# USB3.net
KiCad netlist of a schematic drawn in Altium Designer
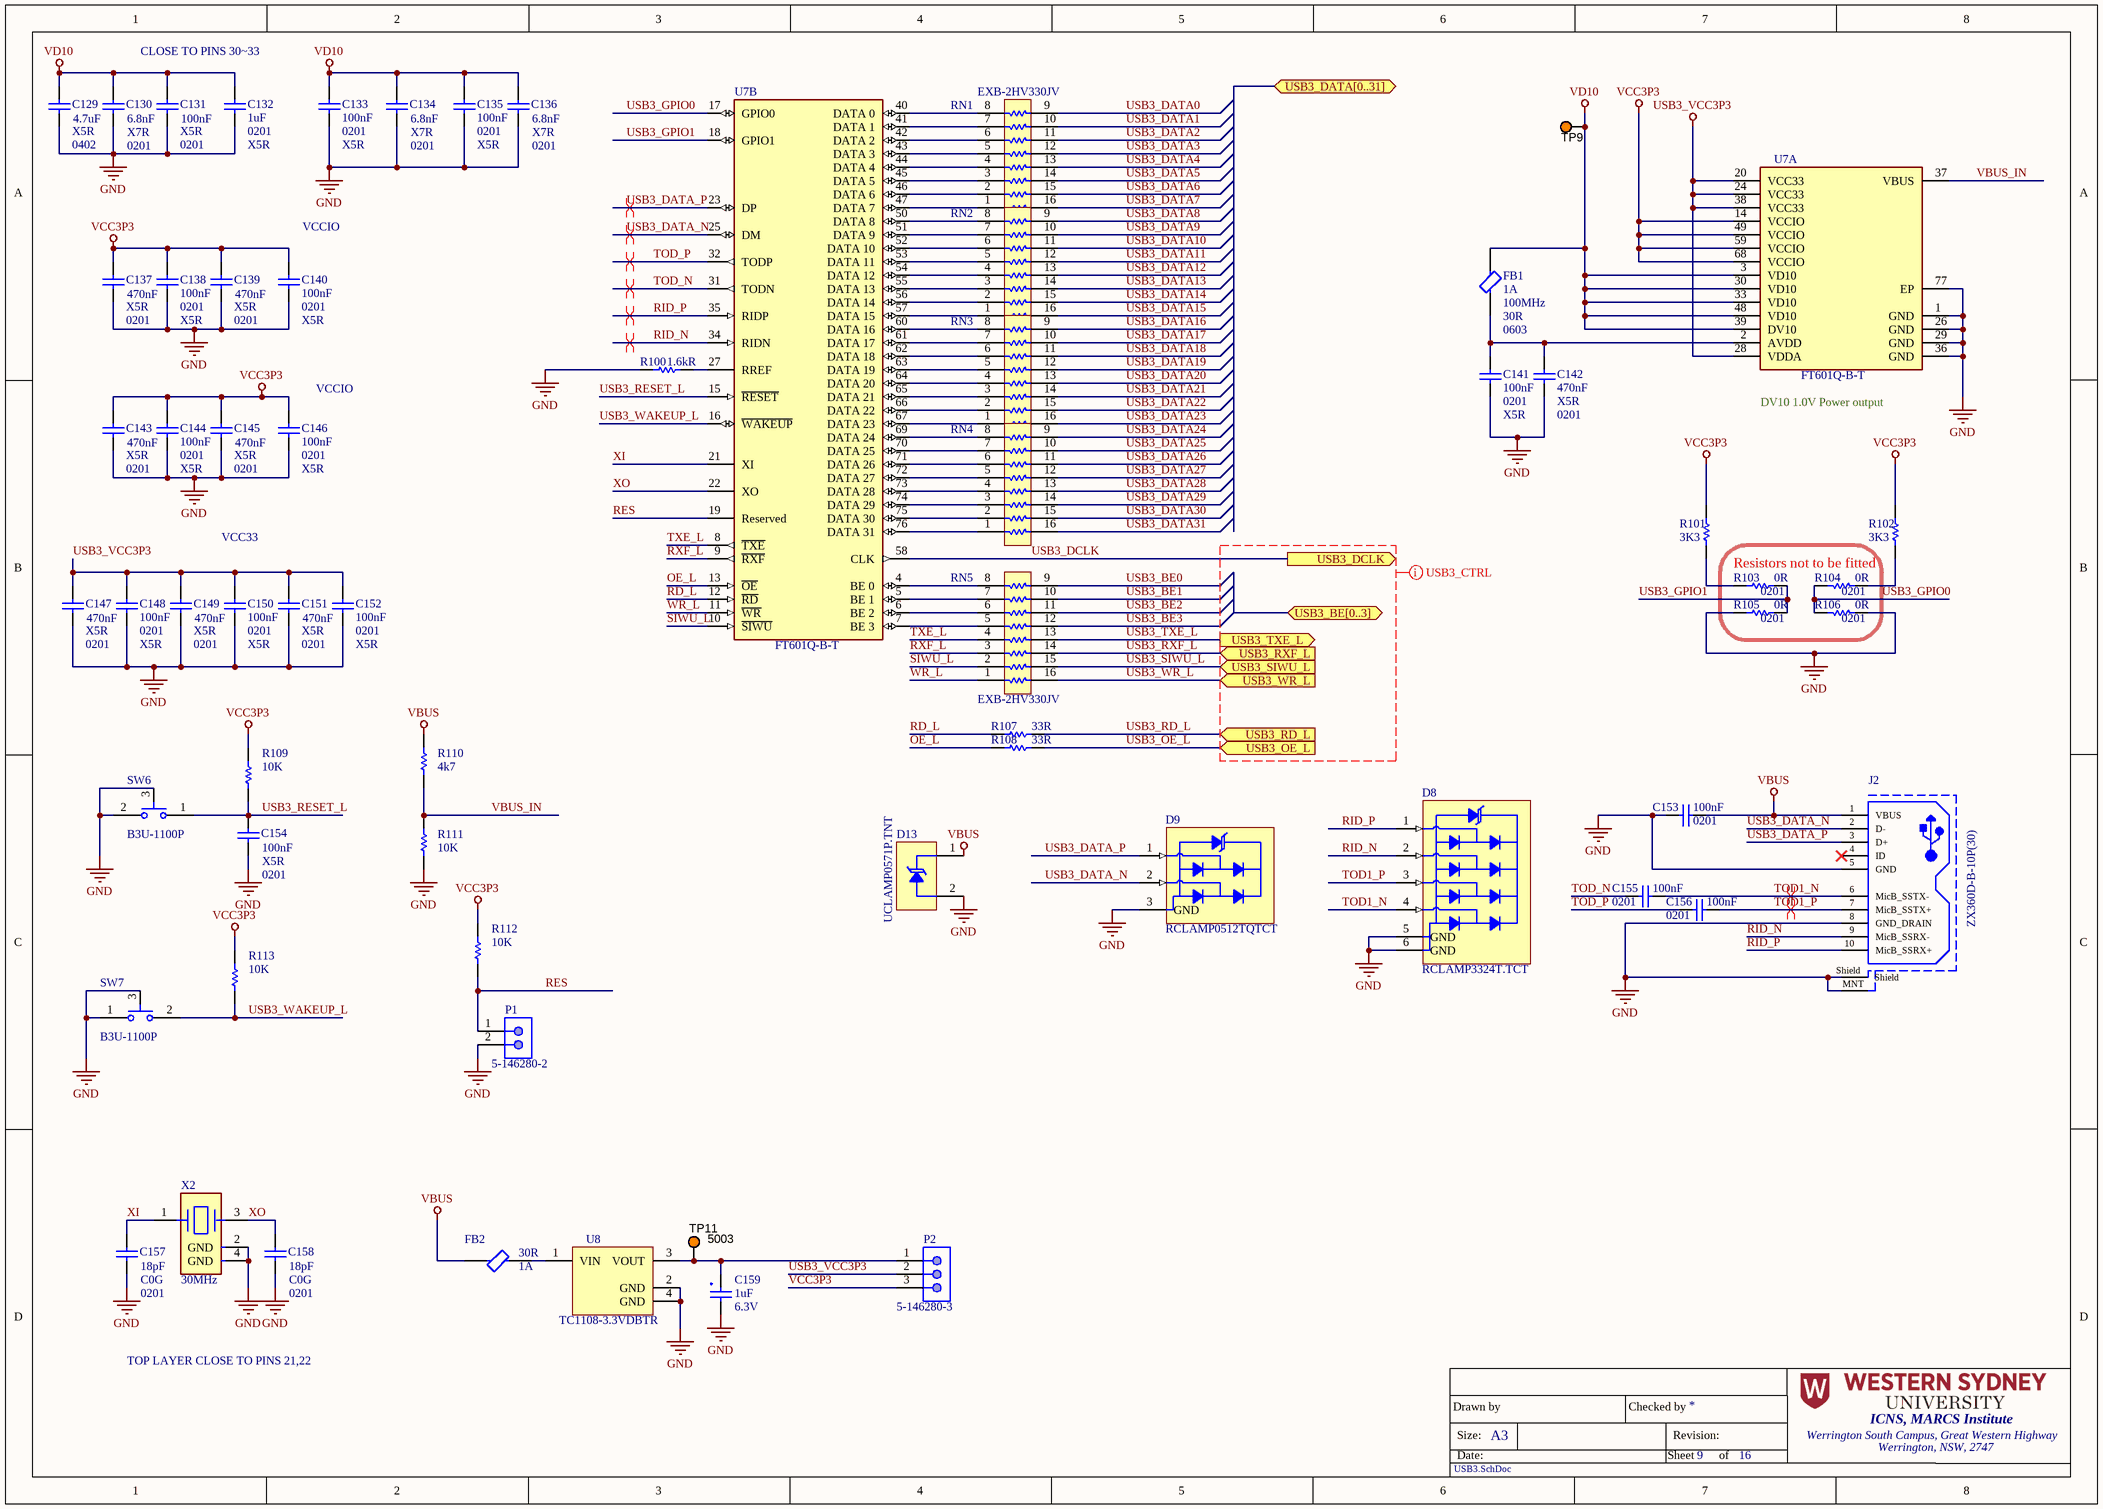
[diagram p0: USB3.SchDoc]

(export (version "E")
  (design (tool "Eeschema 10.0.6"))
  (components
    (comp (ref "C129")
      (value "C1005X5R1A475K050BC")
      (footprint "CAP 0402 (1005)")
      (description "Cap Multilayer Ceramic 4.7uF 10 V X5R ±10 % SMT 0402  C Series")
      (fields
        (field (name "TOLERANCE") "10%")
        (field (name "MANUFACTURER") "TDK")
        (field (name "CAPACITANCE") "4.7uF")
        (field (name "DIELECTRIC") "X5R")
        (field (name "CASE CODE (IMPERIAL)") "0402")
        (field (name "SOURCE") "ICNS_PropheseeLib.SchLib")
      )
      (libsource (lib "") (part "Symbol_2"))
    )
    (comp (ref "C130")
      (value "GRM033R71A682KA01D")
      (footprint "CAP 0201 (0603)")
      (description "Cap Multilayer Ceramic 6.8nF 10V X7R SMT 0201 ±10% Tolerance")
      (fields
        (field (name "TOLERANCE") "10%")
        (field (name "DIELECTRIC") "X7R")
        (field (name "CAPACITANCE") "6.8nF")
        (field (name "CASE CODE (IMPERIAL)") "0201")
        (field (name "MANUFACTURER") "Murata")
        (field (name "SOURCE") "ICNS_PropheseeLib.SchLib")
      )
      (libsource (lib "") (part "Symbol_1"))
    )
    (comp (ref "C131")
      (value "CL03A104KP3NNNC")
      (footprint "CAP 0201 (0603)")
      (description "Cap Ceramic 0.1uF 10V X5R 10% Pad SMD 0201 85C T/R")
      (fields
        (field (name "TOLERANCE") "10%")
        (field (name "MANUFACTURER") "Samsung")
        (field (name "CAPACITANCE") "100nF")
        (field (name "DIELECTRIC") "X5R")
        (field (name "CASE CODE (IMPERIAL)") "0201")
        (field (name "SOURCE") "ICNS_PropheseeLib.SchLib")
      )
      (libsource (lib "Western Sydney University - ICNS") (part "CL03A104KP3NNNC"))
    )
    (comp (ref "C132")
      (value "CL03A105KP3NSNC")
      (footprint "CAP 0201 (0603)")
      (description "Cap Ceramic 1uF 10V X5R 10% Pad SMD 0201 85C T/R")
      (fields
        (field (name "TOLERANCE") "10%")
        (field (name "MANUFACTURER") "Samsung")
        (field (name "CAPACITANCE") "1uF")
        (field (name "CASE CODE (IMPERIAL)") "0201")
        (field (name "DIELECTRIC") "X5R")
        (field (name "SOURCE") "ICNS_PropheseeLib.SchLib")
      )
      (libsource (lib "") (part "Symbol_2"))
    )
    (comp (ref "C133")
      (value "CL03A104KP3NNNC")
      (footprint "CAP 0201 (0603)")
      (description "Cap Ceramic 0.1uF 10V X5R 10% Pad SMD 0201 85C T/R")
      (fields
        (field (name "TOLERANCE") "10%")
        (field (name "MANUFACTURER") "Samsung")
        (field (name "CAPACITANCE") "100nF")
        (field (name "CASE CODE (IMPERIAL)") "0201")
        (field (name "DIELECTRIC") "X5R")
        (field (name "SOURCE") "ICNS_PropheseeLib.SchLib")
      )
      (libsource (lib "Western Sydney University - ICNS") (part "CL03A104KP3NNNC"))
    )
    (comp (ref "C134")
      (value "GRM033R71A682KA01D")
      (footprint "CAP 0201 (0603)")
      (description "Cap Multilayer Ceramic 6.8nF 10V X7R SMT 0201 ±10% Tolerance")
      (fields
        (field (name "TOLERANCE") "10%")
        (field (name "DIELECTRIC") "X7R")
        (field (name "CAPACITANCE") "6.8nF")
        (field (name "CASE CODE (IMPERIAL)") "0201")
        (field (name "MANUFACTURER") "Murata")
        (field (name "SOURCE") "ICNS_PropheseeLib.SchLib")
      )
      (libsource (lib "") (part "Symbol_1"))
    )
    (comp (ref "C135")
      (value "CL03A104KP3NNNC")
      (footprint "CAP 0201 (0603)")
      (description "Cap Ceramic 0.1uF 10V X5R 10% Pad SMD 0201 85C T/R")
      (fields
        (field (name "TOLERANCE") "10%")
        (field (name "MANUFACTURER") "Samsung")
        (field (name "CAPACITANCE") "100nF")
        (field (name "CASE CODE (IMPERIAL)") "0201")
        (field (name "DIELECTRIC") "X5R")
        (field (name "SOURCE") "ICNS_PropheseeLib.SchLib")
      )
      (libsource (lib "Western Sydney University - ICNS") (part "CL03A104KP3NNNC"))
    )
    (comp (ref "C136")
      (value "GRM033R71A682KA01D")
      (footprint "CAP 0201 (0603)")
      (description "Cap Multilayer Ceramic 6.8nF 10V X7R SMT 0201 ±10% Tolerance")
      (fields
        (field (name "TOLERANCE") "10%")
        (field (name "DIELECTRIC") "X7R")
        (field (name "CAPACITANCE") "6.8nF")
        (field (name "CASE CODE (IMPERIAL)") "0201")
        (field (name "MANUFACTURER") "Murata")
        (field (name "SOURCE") "ICNS_PropheseeLib.SchLib")
      )
      (libsource (lib "") (part "Symbol_1"))
    )
    (comp (ref "C137")
      (value "LMK063BBJ474KPLF")
      (footprint "CAP 0201 (0603)")
      (description "Cap Multilayer Ceramic 0.47 uF 10V X5R  0201 10% RoHS  (High dielectric type)")
      (fields
        (field (name "MANUFACTURER") "Taiyo Yuden")
        (field (name "CAPACITANCE") "470nF")
        (field (name "DIELECTRIC") "X5R")
        (field (name "CASE CODE (IMPERIAL)") "0201")
        (field (name "SOURCE") "ICNS_PropheseeLib.SchLib")
      )
      (libsource (lib "Western Sydney University - ICNS") (part "LMK063BBJ474KPLF"))
    )
    (comp (ref "C138")
      (value "CL03A104KP3NNNC")
      (footprint "CAP 0201 (0603)")
      (description "Cap Ceramic 0.1uF 10V X5R 10% Pad SMD 0201 85C T/R")
      (fields
        (field (name "TOLERANCE") "10%")
        (field (name "MANUFACTURER") "Samsung")
        (field (name "CAPACITANCE") "100nF")
        (field (name "CASE CODE (IMPERIAL)") "0201")
        (field (name "DIELECTRIC") "X5R")
        (field (name "SOURCE") "ICNS_PropheseeLib.SchLib")
      )
      (libsource (lib "Western Sydney University - ICNS") (part "CL03A104KP3NNNC"))
    )
    (comp (ref "C139")
      (value "LMK063BBJ474KPLF")
      (footprint "CAP 0201 (0603)")
      (description "Cap Multilayer Ceramic 0.47 uF 10V X5R  0201 10% RoHS  (High dielectric type)")
      (fields
        (field (name "MANUFACTURER") "Taiyo Yuden")
        (field (name "CAPACITANCE") "470nF")
        (field (name "DIELECTRIC") "X5R")
        (field (name "CASE CODE (IMPERIAL)") "0201")
        (field (name "SOURCE") "ICNS_PropheseeLib.SchLib")
      )
      (libsource (lib "Western Sydney University - ICNS") (part "LMK063BBJ474KPLF"))
    )
    (comp (ref "C140")
      (value "CL03A104KP3NNNC")
      (footprint "CAP 0201 (0603)")
      (description "Cap Ceramic 0.1uF 10V X5R 10% Pad SMD 0201 85C T/R")
      (fields
        (field (name "TOLERANCE") "10%")
        (field (name "MANUFACTURER") "Samsung")
        (field (name "CAPACITANCE") "100nF")
        (field (name "CASE CODE (IMPERIAL)") "0201")
        (field (name "DIELECTRIC") "X5R")
        (field (name "SOURCE") "ICNS_PropheseeLib.SchLib")
      )
      (libsource (lib "Western Sydney University - ICNS") (part "CL03A104KP3NNNC"))
    )
    (comp (ref "C141")
      (value "CL03A104KP3NNNC")
      (footprint "CAP 0201 (0603)")
      (description "Cap Ceramic 0.1uF 10V X5R 10% Pad SMD 0201 85C T/R")
      (fields
        (field (name "TOLERANCE") "10%")
        (field (name "MANUFACTURER") "Samsung")
        (field (name "CAPACITANCE") "100nF")
        (field (name "CASE CODE (IMPERIAL)") "0201")
        (field (name "DIELECTRIC") "X5R")
        (field (name "SOURCE") "ICNS_PropheseeLib.SchLib")
      )
      (libsource (lib "Western Sydney University - ICNS") (part "CL03A104KP3NNNC"))
    )
    (comp (ref "C142")
      (value "LMK063BBJ474KPLF")
      (footprint "CAP 0201 (0603)")
      (description "Cap Multilayer Ceramic 0.47 uF 10V X5R  0201 10% RoHS  (High dielectric type)")
      (fields
        (field (name "MANUFACTURER") "Taiyo Yuden")
        (field (name "CAPACITANCE") "470nF")
        (field (name "DIELECTRIC") "X5R")
        (field (name "CASE CODE (IMPERIAL)") "0201")
        (field (name "SOURCE") "ICNS_PropheseeLib.SchLib")
      )
      (libsource (lib "Western Sydney University - ICNS") (part "LMK063BBJ474KPLF"))
    )
    (comp (ref "C143")
      (value "LMK063BBJ474KPLF")
      (footprint "CAP 0201 (0603)")
      (description "Cap Multilayer Ceramic 0.47 uF 10V X5R  0201 10% RoHS  (High dielectric type)")
      (fields
        (field (name "MANUFACTURER") "Taiyo Yuden")
        (field (name "CAPACITANCE") "470nF")
        (field (name "DIELECTRIC") "X5R")
        (field (name "CASE CODE (IMPERIAL)") "0201")
        (field (name "SOURCE") "ICNS_PropheseeLib.SchLib")
      )
      (libsource (lib "Western Sydney University - ICNS") (part "LMK063BBJ474KPLF"))
    )
    (comp (ref "C144")
      (value "CL03A104KP3NNNC")
      (footprint "CAP 0201 (0603)")
      (description "Cap Ceramic 0.1uF 10V X5R 10% Pad SMD 0201 85C T/R")
      (fields
        (field (name "TOLERANCE") "10%")
        (field (name "MANUFACTURER") "Samsung")
        (field (name "CAPACITANCE") "100nF")
        (field (name "CASE CODE (IMPERIAL)") "0201")
        (field (name "DIELECTRIC") "X5R")
        (field (name "SOURCE") "ICNS_PropheseeLib.SchLib")
      )
      (libsource (lib "Western Sydney University - ICNS") (part "CL03A104KP3NNNC"))
    )
    (comp (ref "C145")
      (value "LMK063BBJ474KPLF")
      (footprint "CAP 0201 (0603)")
      (description "Cap Multilayer Ceramic 0.47 uF 10V X5R  0201 10% RoHS  (High dielectric type)")
      (fields
        (field (name "MANUFACTURER") "Taiyo Yuden")
        (field (name "CAPACITANCE") "470nF")
        (field (name "DIELECTRIC") "X5R")
        (field (name "CASE CODE (IMPERIAL)") "0201")
        (field (name "SOURCE") "ICNS_PropheseeLib.SchLib")
      )
      (libsource (lib "Western Sydney University - ICNS") (part "LMK063BBJ474KPLF"))
    )
    (comp (ref "C146")
      (value "CL03A104KP3NNNC")
      (footprint "CAP 0201 (0603)")
      (description "Cap Ceramic 0.1uF 10V X5R 10% Pad SMD 0201 85C T/R")
      (fields
        (field (name "TOLERANCE") "10%")
        (field (name "MANUFACTURER") "Samsung")
        (field (name "CAPACITANCE") "100nF")
        (field (name "CASE CODE (IMPERIAL)") "0201")
        (field (name "DIELECTRIC") "X5R")
        (field (name "SOURCE") "ICNS_PropheseeLib.SchLib")
      )
      (libsource (lib "Western Sydney University - ICNS") (part "CL03A104KP3NNNC"))
    )
    (comp (ref "C147")
      (value "LMK063BBJ474KPLF")
      (footprint "CAP 0201 (0603)")
      (description "Cap Multilayer Ceramic 0.47 uF 10V X5R  0201 10% RoHS  (High dielectric type)")
      (fields
        (field (name "MANUFACTURER") "Taiyo Yuden")
        (field (name "CAPACITANCE") "470nF")
        (field (name "DIELECTRIC") "X5R")
        (field (name "CASE CODE (IMPERIAL)") "0201")
        (field (name "SOURCE") "ICNS_PropheseeLib.SchLib")
      )
      (libsource (lib "Western Sydney University - ICNS") (part "LMK063BBJ474KPLF"))
    )
    (comp (ref "C148")
      (value "CL03A104KP3NNNC")
      (footprint "CAP 0201 (0603)")
      (description "Cap Ceramic 0.1uF 10V X5R 10% Pad SMD 0201 85C T/R")
      (fields
        (field (name "TOLERANCE") "10%")
        (field (name "MANUFACTURER") "Samsung")
        (field (name "CAPACITANCE") "100nF")
        (field (name "CASE CODE (IMPERIAL)") "0201")
        (field (name "DIELECTRIC") "X5R")
        (field (name "SOURCE") "ICNS_PropheseeLib.SchLib")
      )
      (libsource (lib "Western Sydney University - ICNS") (part "CL03A104KP3NNNC"))
    )
    (comp (ref "C149")
      (value "LMK063BBJ474KPLF")
      (footprint "CAP 0201 (0603)")
      (description "Cap Multilayer Ceramic 0.47 uF 10V X5R  0201 10% RoHS  (High dielectric type)")
      (fields
        (field (name "MANUFACTURER") "Taiyo Yuden")
        (field (name "CAPACITANCE") "470nF")
        (field (name "DIELECTRIC") "X5R")
        (field (name "CASE CODE (IMPERIAL)") "0201")
        (field (name "SOURCE") "ICNS_PropheseeLib.SchLib")
      )
      (libsource (lib "Western Sydney University - ICNS") (part "LMK063BBJ474KPLF"))
    )
    (comp (ref "C150")
      (value "CL03A104KP3NNNC")
      (footprint "CAP 0201 (0603)")
      (description "Cap Ceramic 0.1uF 10V X5R 10% Pad SMD 0201 85C T/R")
      (fields
        (field (name "TOLERANCE") "10%")
        (field (name "MANUFACTURER") "Samsung")
        (field (name "CAPACITANCE") "100nF")
        (field (name "CASE CODE (IMPERIAL)") "0201")
        (field (name "DIELECTRIC") "X5R")
        (field (name "SOURCE") "ICNS_PropheseeLib.SchLib")
      )
      (libsource (lib "Western Sydney University - ICNS") (part "CL03A104KP3NNNC"))
    )
    (comp (ref "C151")
      (value "LMK063BBJ474KPLF")
      (footprint "CAP 0201 (0603)")
      (description "Cap Multilayer Ceramic 0.47 uF 10V X5R  0201 10% RoHS  (High dielectric type)")
      (fields
        (field (name "MANUFACTURER") "Taiyo Yuden")
        (field (name "CAPACITANCE") "470nF")
        (field (name "DIELECTRIC") "X5R")
        (field (name "CASE CODE (IMPERIAL)") "0201")
        (field (name "SOURCE") "ICNS_PropheseeLib.SchLib")
      )
      (libsource (lib "Western Sydney University - ICNS") (part "LMK063BBJ474KPLF"))
    )
    (comp (ref "C152")
      (value "CL03A104KP3NNNC")
      (footprint "CAP 0201 (0603)")
      (description "Cap Ceramic 0.1uF 10V X5R 10% Pad SMD 0201 85C T/R")
      (fields
        (field (name "TOLERANCE") "10%")
        (field (name "MANUFACTURER") "Samsung")
        (field (name "CAPACITANCE") "100nF")
        (field (name "CASE CODE (IMPERIAL)") "0201")
        (field (name "DIELECTRIC") "X5R")
        (field (name "SOURCE") "ICNS_PropheseeLib.SchLib")
      )
      (libsource (lib "Western Sydney University - ICNS") (part "CL03A104KP3NNNC"))
    )
    (comp (ref "C153")
      (value "CL03A104KP3NNNC")
      (footprint "CAP 0201 (0603)")
      (description "Cap Ceramic 0.1uF 10V X5R 10% Pad SMD 0201 85C T/R")
      (fields
        (field (name "CAPACITANCE") "100nF")
        (field (name "MANUFACTURER") "Samsung")
        (field (name "TOLERANCE") "10%")
        (field (name "CASE CODE (IMPERIAL)") "0201")
        (field (name "SOURCE") "ICNS_PropheseeLib.SchLib")
      )
      (libsource (lib "Western Sydney University - ICNS") (part "CL03A104KP3NNNC"))
    )
    (comp (ref "C154")
      (value "CL03A104KP3NNNC")
      (footprint "CAP 0201 (0603)")
      (description "Cap Ceramic 0.1uF 10V X5R 10% Pad SMD 0201 85C T/R")
      (fields
        (field (name "CAPACITANCE") "100nF")
        (field (name "MANUFACTURER") "Samsung")
        (field (name "TOLERANCE") "10%")
        (field (name "CASE CODE (IMPERIAL)") "0201")
        (field (name "DIELECTRIC") "X5R")
        (field (name "SOURCE") "ICNS_PropheseeLib.SchLib")
      )
      (libsource (lib "Western Sydney University - ICNS") (part "CL03A104KP3NNNC"))
    )
    (comp (ref "C155")
      (value "CL03A104KP3NNNC")
      (footprint "CAP 0201 (0603)")
      (description "Cap Ceramic 0.1uF 10V X5R 10% Pad SMD 0201 85C T/R")
      (fields
        (field (name "CAPACITANCE") "100nF")
        (field (name "MANUFACTURER") "Samsung")
        (field (name "TOLERANCE") "10%")
        (field (name "CASE CODE (IMPERIAL)") "0201")
        (field (name "SOURCE") "ICNS_PropheseeLib.SchLib")
      )
      (libsource (lib "Western Sydney University - ICNS") (part "CL03A104KP3NNNC"))
    )
    (comp (ref "C156")
      (value "CL03A104KP3NNNC")
      (footprint "CAP 0201 (0603)")
      (description "Cap Ceramic 0.1uF 10V X5R 10% Pad SMD 0201 85C T/R")
      (fields
        (field (name "CAPACITANCE") "100nF")
        (field (name "MANUFACTURER") "Samsung")
        (field (name "TOLERANCE") "10%")
        (field (name "CASE CODE (IMPERIAL)") "0201")
        (field (name "SOURCE") "ICNS_PropheseeLib.SchLib")
      )
      (libsource (lib "Western Sydney University - ICNS") (part "CL03A104KP3NNNC"))
    )
    (comp (ref "C157")
      (value "18pF")
      (footprint "CAP 0201 (0603)")
      (description "Cap Ceramic 18pF 25V C0G 10% SMD 0201 125°C Paper T/R")
      (fields
        (field (name "DIELECTRIC") "C0G")
        (field (name "CASE/PACKAGE") "0201")
        (field (name "TOLERANCE") "10%")
        (field (name "MANUFACTURER") "KEMET")
        (field (name "SOURCE") "ICNS_PropheseeLib.SchLib")
      )
      (libsource (lib "") (part "Symbol_1"))
    )
    (comp (ref "C158")
      (value "18pF")
      (footprint "CAP 0201 (0603)")
      (description "Cap Ceramic 18pF 25V C0G 10% SMD 0201 125°C Paper T/R")
      (fields
        (field (name "DIELECTRIC") "C0G")
        (field (name "CASE/PACKAGE") "0201")
        (field (name "TOLERANCE") "10%")
        (field (name "MANUFACTURER") "KEMET")
        (field (name "SOURCE") "ICNS_PropheseeLib.SchLib")
      )
      (libsource (lib "") (part "Symbol_1"))
    )
    (comp (ref "C159")
      (value "F380J105MUA")
      (footprint "DFN80P110X55-2N")
      (description "Cap Tant Polymer 1uF 6.3VDC U CASE 20%( 1.1 X 0.6 X 0.55mm) Undertab SMD 1106-06 1.5 Ohm 105C T/R")
      (fields
        (field (name "CAPACITANCE") "1uF")
        (field (name "VOLTAGE RATING") "6.3V")
        (field (name "TOLERANCE") "20%")
        (field (name "MANUFACTURER") "Kyocera AVX")
        (field (name "SOURCE") "ICNS_PropheseeLib.SchLib")
      )
      (libsource (lib "Western Sydney University - ICNS") (part "F380J105MUA"))
    )
    (comp (ref "D8")
      (value "RCLAMP3324T.TCT")
      (footprint "DIO_RCLAMP3324T.TCT")
      (description "TVS DIODE 3.3VWM 10.5VC")
      (fields (field (name "MANUFACTURER") "Semtech") (field (name "SOURCE") "Falcon_Neuro.SchLib"))
      (libsource (lib "Western Sydney University - ICNS") (part "RCLAMP3324P.TNT"))
    )
    (comp (ref "D9")
      (value "RCLAMP0512TQTCT")
      (footprint "DIO_RCLAMP0512TQTCT")
      (description "8.5V Clamp 20A (1.2/50µs) Ipp Tvs Diode Surface Mount SGP1006N3T")
      (fields (field (name "MANUFACTURER") "Semtech") (field (name "SOURCE") "Falcon_Neuro.SchLib"))
      (libsource (lib "Western Sydney University - ICNS") (part "RCLAMP0512TQTCT"))
    )
    (comp (ref "D13")
      (value "UCLAMP0571P.TNT")
      (footprint "uCLAMP0571P")
      (description "ESD Suppressor Diode TVS Uni-Dir 5V Automotive 2-Pin SGP T/R")
      (fields (field (name "MANUFACTURER") "Semtech") (field (name "SOURCE") "Falcon_Neuro.SchLib"))
      (libsource (lib "Western Sydney University - ICNS") (part "UCLAMP0571P.TNT"))
    )
    (comp (ref "FB1")
      (value "BLM18PG300SH1D")
      (footprint "FP-BLM18-0_15-t0_8-IPC_A")
      (description "Ferrite Beads Multi-Layer 30Ohm 100MHz 1A 0.05Ohm DCR 0603 Automotive T/R")
      (fields
        (field (name "MAX CURRENT RATING") "1A")
        (field (name "TEST FREQUENCY") "100MHz")
        (field (name "IMPEDANCE") "30R")
        (field (name "TOLERANCE") "25%")
        (field (name "MANUFACTURER") "Murata")
        (field (name "CASE CODE (IMPERIAL)") "0603")
        (field (name "SOURCE") "ICNS_PropheseeLib.SchLib")
      )
      (libsource (lib "Western Sydney University - ICNS") (part "BLM18PG300SH1D"))
    )
    (comp (ref "FB2")
      (value "BLM18PG300SH1D")
      (footprint "FP-BLM18-0_15-t0_8-IPC_A")
      (description "Ferrite Beads Multi-Layer 30Ohm 100MHz 1A 0.05Ohm DCR 0603 Automotive T/R")
      (fields
        (field (name "TOLERANCE") "25%")
        (field (name "MAX CURRENT RATING") "1A")
        (field (name "IMPEDANCE") "30R")
        (field (name "MANUFACTURER") "Murata")
        (field (name "SOURCE") "ICNS_PropheseeLib.SchLib")
      )
      (libsource (lib "Western Sydney University - ICNS") (part "BLM18PG300SH1D"))
    )
    (comp (ref "J2")
      (value "ZX360D-B-10P(30)")
      (footprint "FP-ZX360D-B-10P-MFG")
      (description "Conn Micro USB 3.0 Type B F 10 POS 0.65mm Solder RA SMD 10 Terminal 1 Port T/R")
      (fields (field (name "MANUFACTURER") "Hirose") (field (name "SOURCE") "ICNS_PropheseeLib.SchLib"))
      (libsource (lib "Western Sydney University - ICNS") (part "ZX360D-B-10P(30)"))
    )
    (comp (ref "P1")
      (value "5-146280-2")
      (footprint "TECO-5-146280-2_V")
      (description "Conn Unshrouded Header HDR 2 POS 2.54mm Solder ST Top Entry Thru-Hole Carton")
      (fields
        (field (name "MANUFACTURER") "TE Connectivity")
        (field (name "SOURCE") "ICNS_PropheseeLib.SchLib")
      )
      (libsource (lib "Western Sydney University - ICNS") (part "5-146280-2"))
    )
    (comp (ref "P2")
      (value "5-146280-3")
      (footprint "TECO-5-146280-3_V")
      (description "PCB Breakaway Header, 0.100 in, 1 Row, 3, 0.12 in, AMPMODU Headers Series")
      (fields
        (field (name "MANUFACTURER") "TE Connectivity")
        (field (name "SOURCE") "ICNS_PropheseeLib.SchLib")
      )
      (libsource (lib "Western Sydney University - ICNS") (part "5-146280-3"))
    )
    (comp (ref "R100")
      (value "ERJ-1GNF1601C")
      (footprint "RES 0201 (0603)")
      (description "Res Thick Film 0201 1.6K Ohm 1% 0.05W(1/20W) ±200ppm/C Pad SMD Automotive T/R")
      (fields
        (field (name "MANUFACTURER") "Panasonic")
        (field (name "RESISTANCE") "1.6kR")
        (field (name "TOLERANCE") "1%")
        (field (name "SOURCE") "ICNS_PropheseeLib.SchLib")
      )
      (libsource (lib "Western Sydney University - ICNS") (part "ERJ-1GNF1601C"))
    )
    (comp (ref "R101")
      (value "3K3")
      (footprint "RES 0201 (0603)")
      (description "Res Thick Film 0201 3.3K Ohm 1% 1/20W ±100ppm/°C Moisture Resistant")
      (fields
        (field (name "MANUFACTURER") "Yageo")
        (field (name "TOLERANCE") "1%")
        (field (name "SOURCE") "ICNS_PropheseeLib.SchLib")
      )
      (libsource (lib "Western Sydney University - ICNS") (part "RC0201FR-073K3L"))
    )
    (comp (ref "R102")
      (value "3K3")
      (footprint "RES 0201 (0603)")
      (description "Res Thick Film 0201 3.3K Ohm 1% 1/20W ±100ppm/°C Moisture Resistant")
      (fields
        (field (name "MANUFACTURER") "Yageo")
        (field (name "TOLERANCE") "1%")
        (field (name "SOURCE") "ICNS_PropheseeLib.SchLib")
      )
      (libsource (lib "Western Sydney University - ICNS") (part "RC0201FR-073K3L"))
    )
    (comp (ref "R103")
      (value "0R")
      (footprint "RES 0201 (0603)")
      (description "Res Thick Film 0201 0 Ohm Sulfur Resistant Pad SMD Automotive T/R")
      (fields
        (field (name "MANUFACTURER") "Yageo")
        (field (name "MANUFACTURER PART NUMBER") "AF0201JR-070RL")
        (field (name "CASE CODE (IMPERIAL)") "0201")
        (field (name "SOURCE") "ICNS_PropheseeLib.SchLib")
      )
      (libsource (lib "Western Sydney University - ICNS") (part "Symbol"))
    )
    (comp (ref "R104")
      (value "0R")
      (footprint "RES 0201 (0603)")
      (description "Res Thick Film 0201 0 Ohm Sulfur Resistant Pad SMD Automotive T/R")
      (fields
        (field (name "MANUFACTURER") "Yageo")
        (field (name "MANUFACTURER PART NUMBER") "AF0201JR-070RL")
        (field (name "CASE CODE (IMPERIAL)") "0201")
        (field (name "SOURCE") "ICNS_PropheseeLib.SchLib")
      )
      (libsource (lib "Western Sydney University - ICNS") (part "Symbol"))
    )
    (comp (ref "R105")
      (value "0R")
      (footprint "RES 0201 (0603)")
      (description "Res Thick Film 0201 0 Ohm Sulfur Resistant Pad SMD Automotive T/R")
      (fields
        (field (name "MANUFACTURER") "Yageo")
        (field (name "MANUFACTURER PART NUMBER") "AF0201JR-070RL")
        (field (name "CASE CODE (IMPERIAL)") "0201")
        (field (name "SOURCE") "ICNS_PropheseeLib.SchLib")
      )
      (libsource (lib "Western Sydney University - ICNS") (part "Symbol"))
    )
    (comp (ref "R106")
      (value "0R")
      (footprint "RES 0201 (0603)")
      (description "Res Thick Film 0201 0 Ohm Sulfur Resistant Pad SMD Automotive T/R")
      (fields
        (field (name "MANUFACTURER") "Yageo")
        (field (name "MANUFACTURER PART NUMBER") "AF0201JR-070RL")
        (field (name "CASE CODE (IMPERIAL)") "0201")
        (field (name "SOURCE") "ICNS_PropheseeLib.SchLib")
      )
      (libsource (lib "Western Sydney University - ICNS") (part "Symbol"))
    )
    (comp (ref "R107")
      (value "33R")
      (footprint "RES 0402 (1005)")
      (description "Res Thick Film 0402 33 Ohm 5% 0.063W(1/16W) ±200ppm/C Pad SMD Automotive T/R")
      (fields
        (field (name "MANUFACTURER PART NUMBER") "CRGCQ0402J33R")
        (field (name "TOLERANCE") "5%")
        (field (name "SOURCE") "ICNS_PropheseeLib.SchLib")
      )
      (libsource (lib "Western Sydney University - ICNS") (part "CRGCQ0402J33R"))
    )
    (comp (ref "R108")
      (value "33R")
      (footprint "RES 0402 (1005)")
      (description "Res Thick Film 0402 33 Ohm 5% 0.063W(1/16W) ±200ppm/C Pad SMD Automotive T/R")
      (fields
        (field (name "MANUFACTURER PART NUMBER") "CRGCQ0402J33R")
        (field (name "TOLERANCE") "5%")
        (field (name "SOURCE") "ICNS_PropheseeLib.SchLib")
      )
      (libsource (lib "Western Sydney University - ICNS") (part "CRGCQ0402J33R"))
    )
    (comp (ref "R109")
      (value "10K")
      (footprint "RES 0201 (0603)")
      (description "Res Thick Film 0201 10K Ohm 1% 0.05W(1/20W) ±200ppm/C Pad SMD Automotive T/R")
      (fields
        (field (name "TOLERANCE") "1%")
        (field (name "MANUFACTURER") "Yageo")
        (field (name "SOURCE") "ICNS_PropheseeLib.SchLib")
      )
      (libsource (lib "Western Sydney University - ICNS") (part "Symbol"))
    )
    (comp (ref "R110")
      (value "4k7")
      (footprint "RES 0201 (0603)")
      (description "Res Thick Film 0201 4.7K Ohm 1% 1/20W ±200ppm/°C Molded SMD Paper T/R")
      (fields
        (field (name "TOLERANCE") "1%")
        (field (name "MANUFACTURER") "Yageo")
        (field (name "SOURCE") "ICNS_PropheseeLib.SchLib")
      )
      (libsource (lib "Western Sydney University - ICNS") (part "Symbol"))
    )
    (comp (ref "R111")
      (value "10K")
      (footprint "RES 0201 (0603)")
      (description "Res Thick Film 0201 10K Ohm 1% 0.05W(1/20W) ±200ppm/C Pad SMD Automotive T/R")
      (fields
        (field (name "TOLERANCE") "1%")
        (field (name "MANUFACTURER") "Yageo")
        (field (name "SOURCE") "ICNS_PropheseeLib.SchLib")
      )
      (libsource (lib "Western Sydney University - ICNS") (part "Symbol"))
    )
    (comp (ref "R112")
      (value "10K")
      (footprint "RES 0201 (0603)")
      (description "Res Thick Film 0201 10K Ohm 1% 0.05W(1/20W) ±200ppm/C Pad SMD Automotive T/R")
      (fields
        (field (name "TOLERANCE") "1%")
        (field (name "MANUFACTURER") "Yageo")
        (field (name "SOURCE") "ICNS_PropheseeLib.SchLib")
      )
      (libsource (lib "Western Sydney University - ICNS") (part "Symbol"))
    )
    (comp (ref "R113")
      (value "10K")
      (footprint "RES 0201 (0603)")
      (description "Res Thick Film 0201 10K Ohm 1% 0.05W(1/20W) ±200ppm/C Pad SMD Automotive T/R")
      (fields
        (field (name "TOLERANCE") "1%")
        (field (name "MANUFACTURER") "Yageo")
        (field (name "SOURCE") "ICNS_PropheseeLib.SchLib")
      )
      (libsource (lib "Western Sydney University - ICNS") (part "Symbol"))
    )
    (comp (ref "RN1")
      (value "EXB-2HV330JV")
      (footprint "PNSC-EXB-2HV330JV-8_N")
      (fields
        (field (name "MANUFACTURER") "Panasonic")
        (field (name "TOLERANCE") "5%")
        (field (name "SOURCE") "ICNS_PropheseeLib.SchLib")
      )
      (libsource (lib "Western Sydney University - ICNS") (part "EXB-2HV330JV"))
    )
    (comp (ref "RN2")
      (value "EXB-2HV330JV")
      (footprint "PNSC-EXB-2HV330JV-8_N")
      (fields
        (field (name "MANUFACTURER") "Panasonic")
        (field (name "TOLERANCE") "5%")
        (field (name "SOURCE") "ICNS_PropheseeLib.SchLib")
      )
      (libsource (lib "Western Sydney University - ICNS") (part "EXB-2HV330JV"))
    )
    (comp (ref "RN3")
      (value "EXB-2HV330JV")
      (footprint "PNSC-EXB-2HV330JV-8_N")
      (fields
        (field (name "MANUFACTURER") "Panasonic")
        (field (name "TOLERANCE") "5%")
        (field (name "SOURCE") "ICNS_PropheseeLib.SchLib")
      )
      (libsource (lib "Western Sydney University - ICNS") (part "EXB-2HV330JV"))
    )
    (comp (ref "RN4")
      (value "EXB-2HV330JV")
      (footprint "PNSC-EXB-2HV330JV-8_N")
      (fields
        (field (name "MANUFACTURER") "Panasonic")
        (field (name "TOLERANCE") "5%")
        (field (name "SOURCE") "ICNS_PropheseeLib.SchLib")
      )
      (libsource (lib "Western Sydney University - ICNS") (part "EXB-2HV330JV"))
    )
    (comp (ref "RN5")
      (value "EXB-2HV330JV")
      (footprint "PNSC-EXB-2HV330JV-8_N")
      (fields
        (field (name "MANUFACTURER") "Panasonic")
        (field (name "TOLERANCE") "5%")
        (field (name "SOURCE") "ICNS_PropheseeLib.SchLib")
      )
      (libsource (lib "Western Sydney University - ICNS") (part "EXB-2HV330JV"))
    )
    (comp (ref "SW6")
      (value "B3U-1100P")
      (footprint "FP-B3U-1100P-MFG")
      (description "Switch Tactile N.O. SPST Round Button Gull Wing 0.05A 12VDC 1.5N SMD Embossed T/R")
      (fields (field (name "MANUFACTURER") "Omron") (field (name "SOURCE") "ICNS_PropheseeLib.SchLib"))
      (libsource (lib "Western Sydney University - ICNS") (part "B3U-1100P"))
    )
    (comp (ref "SW7")
      (value "B3U-1100P")
      (footprint "FP-B3U-1100P-MFG")
      (description "Switch Tactile N.O. SPST Round Button Gull Wing 0.05A 12VDC 1.5N SMD Embossed T/R")
      (fields (field (name "MANUFACTURER") "Omron") (field (name "SOURCE") "ICNS_PropheseeLib.SchLib"))
      (libsource (lib "Western Sydney University - ICNS") (part "B3U-1100P"))
    )
    (comp (ref "TP9")
      (value "5003")
      (footprint "KSTN-5003")
      (description "Test Point, Orange, Height 4.6 mm, Tail Length 3 mm, 1-Pin THD, RoHS")
      (fields (field (name "MANUFACTURER") "Keystone"))
      (libsource (lib "Western Sydney University - ICNS") (part "TESTPOINT_ORANGE"))
    )
    (comp (ref "TP11")
      (value "5003")
      (footprint "KSTN-5003")
      (description "Test Point, Orange, Height 4.6 mm, Tail Length 3 mm, 1-Pin THD, RoHS")
      (fields (field (name "MANUFACTURER") "Keystone"))
      (libsource (lib "Western Sydney University - ICNS") (part "TESTPOINT_ORANGE"))
    )
    (comp (ref "U7")
      (value "FT601Q-B-T")
      (footprint "FP-QFN-76-IPC_A")
      (description "Full Speed/High Speed/Super Speed USB 3.0 to FIFO Bridge USB 2.0/USB 3.0 3.3V Tray 76-Pin QFN EP")
      (fields (field (name "MANUFACTURER") "FTDI") (field (name "SOURCE") "ICNS_PropheseeLib.SchLib"))
      (libsource (lib "Western Sydney University - ICNS") (part "FT601Q-B-T"))
    )
    (comp (ref "U8")
      (value "TC1108-3.3VDBTR")
      (footprint "SOT-223-DB3_L")
      (description "TC1108 Series 300 mA 3.3 V Fixed Output SMT CMOS LDO Regulator - SOT-223")
      (fields (field (name "MANUFACTURER") "Microchip") (field (name "SOURCE") "ICNS_PropheseeLib.SchLib"))
      (libsource (lib "Western Sydney University - ICNS") (part "TC1108-3.3VDBTR"))
    )
    (comp (ref "X2")
      (value "ABM8-30.000MHZ-10-1-U-T")
      (footprint "FP-ABM8-MFG")
      (description "Crystal 30MHz ±10ppm (Tol) ±10ppm (Stability) 10pF FUND 40Ohm 4-Pin Ultra Mini-CSMD T/R")
      (fields
        (field (name "MANUFACTURER") "Abracon")
        (field (name "FREQUENCY") "30MHz")
        (field (name "TOLERANCE") "10ppm")
        (field (name "SOURCE") "ICNS_PropheseeLib.SchLib")
      )
      (libsource (lib "Western Sydney University - ICNS") (part "ABM8-30.000MHZ-10-1-U-T"))
    )
  )
  (nets
    (net (code "1") (name "/OE_L") (class "Default")
      (node (ref "R108") (pin "1") (pinfunction "1_1") (pintype "passive"))
      (node (ref "U7") (pin "13") (pinfunction "~{OE}_13") (pintype "input"))
    )
    (net (code "2") (name "/RD_L") (class "Default")
      (node (ref "R107") (pin "1") (pinfunction "1_1") (pintype "passive"))
      (node (ref "U7") (pin "12") (pinfunction "~{RD}_12") (pintype "input"))
    )
    (net (code "3") (name "/RES") (class "Default")
      (node (ref "P1") (pin "1") (pinfunction "1_1") (pintype "passive"))
      (node (ref "R112") (pin "1") (pinfunction "1_1") (pintype "passive"))
      (node (ref "U7") (pin "19") (pinfunction "Reserved_19") (pintype "passive"))
    )
    (net (code "4") (name "/RID_N") (class "Default")
      (node (ref "D8") (pin "2") (pinfunction "In_2_2") (pintype "input"))
      (node (ref "J2") (pin "9") (pinfunction "MicB_SSRX-_9") (pintype "passive"))
      (node (ref "U7") (pin "34") (pinfunction "RIDN_34") (pintype "input"))
    )
    (net (code "5") (name "/RID_P") (class "Default")
      (node (ref "D8") (pin "1") (pinfunction "In_1_1") (pintype "input"))
      (node (ref "J2") (pin "10") (pinfunction "MicB_SSRX+_10") (pintype "passive"))
      (node (ref "U7") (pin "35") (pinfunction "RIDP_35") (pintype "input"))
    )
    (net (code "6") (name "/RXF_L") (class "Default")
      (node (ref "RN5") (pin "3") (pinfunction "3_3") (pintype "passive"))
      (node (ref "U7") (pin "9") (pinfunction "~{RXF}_9") (pintype "output"))
    )
    (net (code "7") (name "/SIWU_L") (class "Default")
      (node (ref "RN5") (pin "2") (pinfunction "2_2") (pintype "passive"))
      (node (ref "U7") (pin "10") (pinfunction "~{SIWU}_10") (pintype "input"))
    )
    (net (code "8") (name "/TOD1_N") (class "Default")
      (node (ref "C155") (pin "2") (pinfunction "2_2") (pintype "passive"))
      (node (ref "D8") (pin "4") (pinfunction "In_4_4") (pintype "input"))
      (node (ref "J2") (pin "6") (pinfunction "MicB_SSTX-_6") (pintype "passive"))
    )
    (net (code "9") (name "/TOD1_P") (class "Default")
      (node (ref "C156") (pin "2") (pinfunction "2_2") (pintype "passive"))
      (node (ref "D8") (pin "3") (pinfunction "In_3_3") (pintype "input"))
      (node (ref "J2") (pin "7") (pinfunction "MicB_SSTX+_7") (pintype "passive"))
    )
    (net (code "10") (name "/TOD_N") (class "Default")
      (node (ref "C155") (pin "1") (pinfunction "1_1") (pintype "passive"))
      (node (ref "U7") (pin "31") (pinfunction "TODN_31") (pintype "output"))
    )
    (net (code "11") (name "/TOD_P") (class "Default")
      (node (ref "C156") (pin "1") (pinfunction "1_1") (pintype "passive"))
      (node (ref "U7") (pin "32") (pinfunction "TODP_32") (pintype "output"))
    )
    (net (code "12") (name "/TXE_L") (class "Default")
      (node (ref "RN5") (pin "4") (pinfunction "4_4") (pintype "passive"))
      (node (ref "U7") (pin "8") (pinfunction "~{TXE}_8") (pintype "output"))
    )
    (net (code "13") (name "/USB3_BE0") (class "Default")
      (node (ref "RN5") (pin "9") (pinfunction "9_9") (pintype "passive"))
    )
    (net (code "14") (name "/USB3_BE1") (class "Default")
      (node (ref "RN5") (pin "10") (pinfunction "10_10") (pintype "passive"))
    )
    (net (code "15") (name "/USB3_BE2") (class "Default")
      (node (ref "RN5") (pin "11") (pinfunction "11_11") (pintype "passive"))
    )
    (net (code "16") (name "/USB3_BE3") (class "Default")
      (node (ref "RN5") (pin "12") (pinfunction "12_12") (pintype "passive"))
    )
    (net (code "18") (name "/USB3_DATA0") (class "Default")
      (node (ref "RN1") (pin "9") (pinfunction "9_9") (pintype "passive"))
    )
    (net (code "19") (name "/USB3_DATA1") (class "Default")
      (node (ref "RN1") (pin "10") (pinfunction "10_10") (pintype "passive"))
    )
    (net (code "20") (name "/USB3_DATA2") (class "Default")
      (node (ref "RN1") (pin "11") (pinfunction "11_11") (pintype "passive"))
    )
    (net (code "21") (name "/USB3_DATA3") (class "Default")
      (node (ref "RN1") (pin "12") (pinfunction "12_12") (pintype "passive"))
    )
    (net (code "22") (name "/USB3_DATA4") (class "Default")
      (node (ref "RN1") (pin "13") (pinfunction "13_13") (pintype "passive"))
    )
    (net (code "23") (name "/USB3_DATA5") (class "Default")
      (node (ref "RN1") (pin "14") (pinfunction "14_14") (pintype "passive"))
    )
    (net (code "24") (name "/USB3_DATA6") (class "Default")
      (node (ref "RN1") (pin "15") (pinfunction "15_15") (pintype "passive"))
    )
    (net (code "25") (name "/USB3_DATA7") (class "Default")
      (node (ref "RN1") (pin "16") (pinfunction "16_16") (pintype "passive"))
    )
    (net (code "26") (name "/USB3_DATA8") (class "Default")
      (node (ref "RN2") (pin "9") (pinfunction "9_9") (pintype "passive"))
    )
    (net (code "27") (name "/USB3_DATA9") (class "Default")
      (node (ref "RN2") (pin "10") (pinfunction "10_10") (pintype "passive"))
    )
    (net (code "28") (name "/USB3_DATA10") (class "Default")
      (node (ref "RN2") (pin "11") (pinfunction "11_11") (pintype "passive"))
    )
    (net (code "29") (name "/USB3_DATA11") (class "Default")
      (node (ref "RN2") (pin "12") (pinfunction "12_12") (pintype "passive"))
    )
    (net (code "30") (name "/USB3_DATA12") (class "Default")
      (node (ref "RN2") (pin "13") (pinfunction "13_13") (pintype "passive"))
    )
    (net (code "31") (name "/USB3_DATA13") (class "Default")
      (node (ref "RN2") (pin "14") (pinfunction "14_14") (pintype "passive"))
    )
    (net (code "32") (name "/USB3_DATA14") (class "Default")
      (node (ref "RN2") (pin "15") (pinfunction "15_15") (pintype "passive"))
    )
    (net (code "33") (name "/USB3_DATA15") (class "Default")
      (node (ref "RN2") (pin "16") (pinfunction "16_16") (pintype "passive"))
    )
    (net (code "34") (name "/USB3_DATA16") (class "Default")
      (node (ref "RN3") (pin "9") (pinfunction "9_9") (pintype "passive"))
    )
    (net (code "35") (name "/USB3_DATA17") (class "Default")
      (node (ref "RN3") (pin "10") (pinfunction "10_10") (pintype "passive"))
    )
    (net (code "36") (name "/USB3_DATA18") (class "Default")
      (node (ref "RN3") (pin "11") (pinfunction "11_11") (pintype "passive"))
    )
    (net (code "37") (name "/USB3_DATA19") (class "Default")
      (node (ref "RN3") (pin "12") (pinfunction "12_12") (pintype "passive"))
    )
    (net (code "38") (name "/USB3_DATA20") (class "Default")
      (node (ref "RN3") (pin "13") (pinfunction "13_13") (pintype "passive"))
    )
    (net (code "39") (name "/USB3_DATA21") (class "Default")
      (node (ref "RN3") (pin "14") (pinfunction "14_14") (pintype "passive"))
    )
    (net (code "40") (name "/USB3_DATA22") (class "Default")
      (node (ref "RN3") (pin "15") (pinfunction "15_15") (pintype "passive"))
    )
    (net (code "41") (name "/USB3_DATA23") (class "Default")
      (node (ref "RN3") (pin "16") (pinfunction "16_16") (pintype "passive"))
    )
    (net (code "42") (name "/USB3_DATA24") (class "Default")
      (node (ref "RN4") (pin "9") (pinfunction "9_9") (pintype "passive"))
    )
    (net (code "43") (name "/USB3_DATA25") (class "Default")
      (node (ref "RN4") (pin "10") (pinfunction "10_10") (pintype "passive"))
    )
    (net (code "44") (name "/USB3_DATA26") (class "Default")
      (node (ref "RN4") (pin "11") (pinfunction "11_11") (pintype "passive"))
    )
    (net (code "45") (name "/USB3_DATA27") (class "Default")
      (node (ref "RN4") (pin "12") (pinfunction "12_12") (pintype "passive"))
    )
    (net (code "46") (name "/USB3_DATA28") (class "Default")
      (node (ref "RN4") (pin "13") (pinfunction "13_13") (pintype "passive"))
    )
    (net (code "47") (name "/USB3_DATA29") (class "Default")
      (node (ref "RN4") (pin "14") (pinfunction "14_14") (pintype "passive"))
    )
    (net (code "48") (name "/USB3_DATA30") (class "Default")
      (node (ref "RN4") (pin "15") (pinfunction "15_15") (pintype "passive"))
    )
    (net (code "49") (name "/USB3_DATA31") (class "Default")
      (node (ref "RN4") (pin "16") (pinfunction "16_16") (pintype "passive"))
    )
    (net (code "51") (name "/USB3_DATA_N") (class "Default")
      (node (ref "D9") (pin "2") (pinfunction "In_2_2") (pintype "input"))
      (node (ref "J2") (pin "2") (pinfunction "D-_2") (pintype "passive"))
      (node (ref "U7") (pin "25") (pinfunction "DM_25") (pintype "bidirectional"))
    )
    (net (code "52") (name "/USB3_DATA_P") (class "Default")
      (node (ref "D9") (pin "1") (pinfunction "In_1_1") (pintype "input"))
      (node (ref "J2") (pin "3") (pinfunction "D+_3") (pintype "passive"))
      (node (ref "U7") (pin "23") (pinfunction "DP_23") (pintype "bidirectional"))
    )
    (net (code "53") (name "/USB3_DCLK") (class "Default")
      (node (ref "U7") (pin "58") (pinfunction "CLK_58") (pintype "output"))
    )
    (net (code "54") (name "/USB3_GPIO0") (class "Default")
      (node (ref "R104") (pin "2") (pinfunction "2_2") (pintype "passive"))
      (node (ref "R106") (pin "2") (pinfunction "2_2") (pintype "passive"))
      (node (ref "U7") (pin "17") (pinfunction "GPIO0_17") (pintype "bidirectional"))
    )
    (net (code "55") (name "/USB3_GPIO1") (class "Default")
      (node (ref "R103") (pin "2") (pinfunction "2_2") (pintype "passive"))
      (node (ref "R105") (pin "2") (pinfunction "2_2") (pintype "passive"))
      (node (ref "U7") (pin "18") (pinfunction "GPIO1_18") (pintype "bidirectional"))
    )
    (net (code "56") (name "/USB3_OE_L") (class "Default")
      (node (ref "R108") (pin "2") (pinfunction "2_2") (pintype "passive"))
    )
    (net (code "57") (name "/USB3_RD_L") (class "Default")
      (node (ref "R107") (pin "2") (pinfunction "2_2") (pintype "passive"))
    )
    (net (code "58") (name "/USB3_RESET_L") (class "Default")
      (node (ref "C154") (pin "1") (pinfunction "1_1") (pintype "passive"))
      (node (ref "R109") (pin "1") (pinfunction "1_1") (pintype "passive"))
      (node (ref "SW6") (pin "1") (pinfunction "1_1") (pintype "passive"))
      (node (ref "U7") (pin "15") (pinfunction "~{RESET}_15") (pintype "input"))
    )
    (net (code "59") (name "/USB3_RXF_L") (class "Default")
      (node (ref "RN5") (pin "14") (pinfunction "14_14") (pintype "passive"))
    )
    (net (code "60") (name "/USB3_SIWU_L") (class "Default")
      (node (ref "RN5") (pin "15") (pinfunction "15_15") (pintype "passive"))
    )
    (net (code "61") (name "/USB3_TXE_L") (class "Default")
      (node (ref "RN5") (pin "13") (pinfunction "13_13") (pintype "passive"))
    )
    (net (code "62") (name "/USB3_WAKEUP_L") (class "Default")
      (node (ref "R113") (pin "1") (pinfunction "1_1") (pintype "passive"))
      (node (ref "SW7") (pin "2") (pinfunction "2_2") (pintype "passive"))
      (node (ref "U7") (pin "16") (pinfunction "~{WAKEUP}_16") (pintype "bidirectional"))
    )
    (net (code "63") (name "/USB3_WR_L") (class "Default")
      (node (ref "RN5") (pin "16") (pinfunction "16_16") (pintype "passive"))
    )
    (net (code "64") (name "/VBUS_IN") (class "Default")
      (node (ref "R110") (pin "1") (pinfunction "1_1") (pintype "passive"))
      (node (ref "R111") (pin "2") (pinfunction "2_2") (pintype "passive"))
      (node (ref "U7") (pin "37") (pinfunction "VBUS_37") (pintype "power_in"))
    )
    (net (code "65") (name "/WR_L") (class "Default")
      (node (ref "RN5") (pin "1") (pinfunction "1_1") (pintype "passive"))
      (node (ref "U7") (pin "11") (pinfunction "~{WR}_11") (pintype "input"))
    )
    (net (code "66") (name "/XI") (class "Default")
      (node (ref "C157") (pin "1") (pinfunction "1_1") (pintype "passive"))
      (node (ref "U7") (pin "21") (pinfunction "XI_21") (pintype "passive"))
      (node (ref "X2") (pin "1") (pinfunction "1_1") (pintype "passive"))
    )
    (net (code "67") (name "/XO") (class "Default")
      (node (ref "C158") (pin "1") (pinfunction "1_1") (pintype "passive"))
      (node (ref "U7") (pin "22") (pinfunction "XO_22") (pintype "passive"))
      (node (ref "X2") (pin "3") (pinfunction "3_3") (pintype "passive"))
    )
    (net (code "68") (name "GND") (class "Default")
      (node (ref "C129") (pin "2") (pinfunction "2_2") (pintype "passive"))
      (node (ref "C130") (pin "2") (pinfunction "2_2") (pintype "passive"))
      (node (ref "C131") (pin "2") (pinfunction "2_2") (pintype "passive"))
      (node (ref "C132") (pin "1") (pinfunction "1_1") (pintype "passive"))
      (node (ref "C133") (pin "2") (pinfunction "2_2") (pintype "passive"))
      (node (ref "C134") (pin "2") (pinfunction "2_2") (pintype "passive"))
      (node (ref "C135") (pin "2") (pinfunction "2_2") (pintype "passive"))
      (node (ref "C136") (pin "2") (pinfunction "2_2") (pintype "passive"))
      (node (ref "C137") (pin "2") (pinfunction "2_2") (pintype "passive"))
      (node (ref "C138") (pin "2") (pinfunction "2_2") (pintype "passive"))
      (node (ref "C139") (pin "2") (pinfunction "2_2") (pintype "passive"))
      (node (ref "C140") (pin "2") (pinfunction "2_2") (pintype "passive"))
      (node (ref "C141") (pin "2") (pinfunction "2_2") (pintype "passive"))
      (node (ref "C142") (pin "2") (pinfunction "2_2") (pintype "passive"))
      (node (ref "C143") (pin "2") (pinfunction "2_2") (pintype "passive"))
      (node (ref "C144") (pin "2") (pinfunction "2_2") (pintype "passive"))
      (node (ref "C145") (pin "2") (pinfunction "2_2") (pintype "passive"))
      (node (ref "C146") (pin "2") (pinfunction "2_2") (pintype "passive"))
      (node (ref "C147") (pin "2") (pinfunction "2_2") (pintype "passive"))
      (node (ref "C148") (pin "2") (pinfunction "2_2") (pintype "passive"))
      (node (ref "C149") (pin "2") (pinfunction "2_2") (pintype "passive"))
      (node (ref "C150") (pin "2") (pinfunction "2_2") (pintype "passive"))
      (node (ref "C151") (pin "2") (pinfunction "2_2") (pintype "passive"))
      (node (ref "C152") (pin "2") (pinfunction "2_2") (pintype "passive"))
      (node (ref "C153") (pin "1") (pinfunction "1_1") (pintype "passive"))
      (node (ref "C154") (pin "2") (pinfunction "2_2") (pintype "passive"))
      (node (ref "C157") (pin "2") (pinfunction "2_2") (pintype "passive"))
      (node (ref "C158") (pin "2") (pinfunction "2_2") (pintype "passive"))
      (node (ref "C159") (pin "2") (pinfunction "2_2") (pintype "passive"))
      (node (ref "D13") (pin "2") (pinfunction "In_2_2") (pintype "passive"))
      (node (ref "D8") (pin "5") (pinfunction "GND_5") (pintype "passive"))
      (node (ref "D8") (pin "6") (pinfunction "GND_6") (pintype "passive"))
      (node (ref "D9") (pin "3") (pinfunction "GND_3") (pintype "passive"))
      (node (ref "J2") (pin "5") (pinfunction "GND_5") (pintype "passive"))
      (node (ref "J2") (pin "8") (pinfunction "GND_DRAIN_8") (pintype "passive"))
      (node (ref "J2") (pin "MNT") (pinfunction "MNT_MNT") (pintype "passive"))
      (node (ref "J2") (pin "Shield") (pinfunction "Shield_Shield") (pintype "passive"))
      (node (ref "P1") (pin "2") (pinfunction "2_2") (pintype "passive"))
      (node (ref "R100") (pin "1") (pinfunction "1_1") (pintype "passive"))
      (node (ref "R105") (pin "1") (pinfunction "1_1") (pintype "passive"))
      (node (ref "R106") (pin "1") (pinfunction "1_1") (pintype "passive"))
      (node (ref "R111") (pin "1") (pinfunction "1_1") (pintype "passive"))
      (node (ref "SW6") (pin "2") (pinfunction "2_2") (pintype "passive"))
      (node (ref "SW6") (pin "3") (pinfunction "3_3") (pintype "passive"))
      (node (ref "SW7") (pin "1") (pinfunction "1_1") (pintype "passive"))
      (node (ref "SW7") (pin "3") (pinfunction "3_3") (pintype "passive"))
      (node (ref "U7") (pin "1") (pinfunction "GND_1") (pintype "power_in"))
      (node (ref "U7") (pin "26") (pinfunction "GND_26") (pintype "power_in"))
      (node (ref "U7") (pin "29") (pinfunction "GND_29") (pintype "power_in"))
      (node (ref "U7") (pin "36") (pinfunction "GND_36") (pintype "power_in"))
      (node (ref "U7") (pin "77") (pinfunction "EP_77") (pintype "power_in"))
      (node (ref "U8") (pin "2") (pinfunction "GND_2") (pintype "power_in"))
      (node (ref "U8") (pin "4") (pinfunction "GND_4") (pintype "power_in"))
      (node (ref "X2") (pin "2") (pinfunction "GND_2") (pintype "power_in"))
      (node (ref "X2") (pin "4") (pinfunction "GND_4") (pintype "power_in"))
    )
    (net (code "69") (name "Net-(R101-Pad1)") (class "Default")
      (node (ref "R101") (pin "1") (pinfunction "1_1") (pintype "passive"))
      (node (ref "R103") (pin "1") (pinfunction "1_1") (pintype "passive"))
    )
    (net (code "70") (name "Net-(R102-Pad1)") (class "Default")
      (node (ref "R102") (pin "1") (pinfunction "1_1") (pintype "passive"))
      (node (ref "R104") (pin "1") (pinfunction "1_1") (pintype "passive"))
    )
    (net (code "71") (name "Net-(U7A-AVDD)") (class "Default")
      (node (ref "C141") (pin "1") (pinfunction "1_1") (pintype "passive"))
      (node (ref "C142") (pin "1") (pinfunction "1_1") (pintype "passive"))
      (node (ref "FB1") (pin "1") (pinfunction "1_1") (pintype "passive"))
      (node (ref "U7") (pin "2") (pinfunction "AVDD_2") (pintype "power_in"))
    )
    (net (code "72") (name "Net-(U7B-BE_0)") (class "Default")
      (node (ref "RN5") (pin "8") (pinfunction "8_8") (pintype "passive"))
      (node (ref "U7") (pin "4") (pinfunction "BE_0_4") (pintype "bidirectional"))
    )
    (net (code "73") (name "Net-(U7B-BE_1)") (class "Default")
      (node (ref "RN5") (pin "7") (pinfunction "7_7") (pintype "passive"))
      (node (ref "U7") (pin "5") (pinfunction "BE_1_5") (pintype "bidirectional"))
    )
    (net (code "74") (name "Net-(U7B-BE_2)") (class "Default")
      (node (ref "RN5") (pin "6") (pinfunction "6_6") (pintype "passive"))
      (node (ref "U7") (pin "6") (pinfunction "BE_2_6") (pintype "bidirectional"))
    )
    (net (code "75") (name "Net-(U7B-BE_3)") (class "Default")
      (node (ref "RN5") (pin "5") (pinfunction "5_5") (pintype "passive"))
      (node (ref "U7") (pin "7") (pinfunction "BE_3_7") (pintype "bidirectional"))
    )
    (net (code "76") (name "Net-(U7B-DATA_0)") (class "Default")
      (node (ref "RN1") (pin "8") (pinfunction "8_8") (pintype "passive"))
      (node (ref "U7") (pin "40") (pinfunction "DATA_0_40") (pintype "bidirectional"))
    )
    (net (code "77") (name "Net-(U7B-DATA_1)") (class "Default")
      (node (ref "RN1") (pin "7") (pinfunction "7_7") (pintype "passive"))
      (node (ref "U7") (pin "41") (pinfunction "DATA_1_41") (pintype "bidirectional"))
    )
    (net (code "78") (name "Net-(U7B-DATA_2)") (class "Default")
      (node (ref "RN1") (pin "6") (pinfunction "6_6") (pintype "passive"))
      (node (ref "U7") (pin "42") (pinfunction "DATA_2_42") (pintype "bidirectional"))
    )
    (net (code "79") (name "Net-(U7B-DATA_3)") (class "Default")
      (node (ref "RN1") (pin "5") (pinfunction "5_5") (pintype "passive"))
      (node (ref "U7") (pin "43") (pinfunction "DATA_3_43") (pintype "bidirectional"))
    )
    (net (code "80") (name "Net-(U7B-DATA_4)") (class "Default")
      (node (ref "RN1") (pin "4") (pinfunction "4_4") (pintype "passive"))
      (node (ref "U7") (pin "44") (pinfunction "DATA_4_44") (pintype "bidirectional"))
    )
    (net (code "81") (name "Net-(U7B-DATA_5)") (class "Default")
      (node (ref "RN1") (pin "3") (pinfunction "3_3") (pintype "passive"))
      (node (ref "U7") (pin "45") (pinfunction "DATA_5_45") (pintype "bidirectional"))
    )
    (net (code "82") (name "Net-(U7B-DATA_6)") (class "Default")
      (node (ref "RN1") (pin "2") (pinfunction "2_2") (pintype "passive"))
      (node (ref "U7") (pin "46") (pinfunction "DATA_6_46") (pintype "bidirectional"))
    )
    (net (code "83") (name "Net-(U7B-DATA_7)") (class "Default")
      (node (ref "RN1") (pin "1") (pinfunction "1_1") (pintype "passive"))
      (node (ref "U7") (pin "47") (pinfunction "DATA_7_47") (pintype "bidirectional"))
    )
    (net (code "84") (name "Net-(U7B-DATA_8)") (class "Default")
      (node (ref "RN2") (pin "8") (pinfunction "8_8") (pintype "passive"))
      (node (ref "U7") (pin "50") (pinfunction "DATA_8_50") (pintype "bidirectional"))
    )
    (net (code "85") (name "Net-(U7B-DATA_9)") (class "Default")
      (node (ref "RN2") (pin "7") (pinfunction "7_7") (pintype "passive"))
      (node (ref "U7") (pin "51") (pinfunction "DATA_9_51") (pintype "bidirectional"))
    )
    (net (code "86") (name "Net-(U7B-DATA_10)") (class "Default")
      (node (ref "RN2") (pin "6") (pinfunction "6_6") (pintype "passive"))
      (node (ref "U7") (pin "52") (pinfunction "DATA_10_52") (pintype "bidirectional"))
    )
    (net (code "87") (name "Net-(U7B-DATA_11)") (class "Default")
      (node (ref "RN2") (pin "5") (pinfunction "5_5") (pintype "passive"))
      (node (ref "U7") (pin "53") (pinfunction "DATA_11_53") (pintype "bidirectional"))
    )
    (net (code "88") (name "Net-(U7B-DATA_12)") (class "Default")
      (node (ref "RN2") (pin "4") (pinfunction "4_4") (pintype "passive"))
      (node (ref "U7") (pin "54") (pinfunction "DATA_12_54") (pintype "bidirectional"))
    )
    (net (code "89") (name "Net-(U7B-DATA_13)") (class "Default")
      (node (ref "RN2") (pin "3") (pinfunction "3_3") (pintype "passive"))
      (node (ref "U7") (pin "55") (pinfunction "DATA_13_55") (pintype "bidirectional"))
    )
    (net (code "90") (name "Net-(U7B-DATA_14)") (class "Default")
      (node (ref "RN2") (pin "2") (pinfunction "2_2") (pintype "passive"))
      (node (ref "U7") (pin "56") (pinfunction "DATA_14_56") (pintype "bidirectional"))
    )
    (net (code "91") (name "Net-(U7B-DATA_15)") (class "Default")
      (node (ref "RN2") (pin "1") (pinfunction "1_1") (pintype "passive"))
      (node (ref "U7") (pin "57") (pinfunction "DATA_15_57") (pintype "bidirectional"))
    )
    (net (code "92") (name "Net-(U7B-DATA_16)") (class "Default")
      (node (ref "RN3") (pin "8") (pinfunction "8_8") (pintype "passive"))
      (node (ref "U7") (pin "60") (pinfunction "DATA_16_60") (pintype "bidirectional"))
    )
    (net (code "93") (name "Net-(U7B-DATA_17)") (class "Default")
      (node (ref "RN3") (pin "7") (pinfunction "7_7") (pintype "passive"))
      (node (ref "U7") (pin "61") (pinfunction "DATA_17_61") (pintype "bidirectional"))
    )
    (net (code "94") (name "Net-(U7B-DATA_18)") (class "Default")
      (node (ref "RN3") (pin "6") (pinfunction "6_6") (pintype "passive"))
      (node (ref "U7") (pin "62") (pinfunction "DATA_18_62") (pintype "bidirectional"))
    )
    (net (code "95") (name "Net-(U7B-DATA_19)") (class "Default")
      (node (ref "RN3") (pin "5") (pinfunction "5_5") (pintype "passive"))
      (node (ref "U7") (pin "63") (pinfunction "DATA_19_63") (pintype "bidirectional"))
    )
    (net (code "96") (name "Net-(U7B-DATA_20)") (class "Default")
      (node (ref "RN3") (pin "4") (pinfunction "4_4") (pintype "passive"))
      (node (ref "U7") (pin "64") (pinfunction "DATA_20_64") (pintype "bidirectional"))
    )
    (net (code "97") (name "Net-(U7B-DATA_21)") (class "Default")
      (node (ref "RN3") (pin "3") (pinfunction "3_3") (pintype "passive"))
      (node (ref "U7") (pin "65") (pinfunction "DATA_21_65") (pintype "bidirectional"))
    )
    (net (code "98") (name "Net-(U7B-DATA_22)") (class "Default")
      (node (ref "RN3") (pin "2") (pinfunction "2_2") (pintype "passive"))
      (node (ref "U7") (pin "66") (pinfunction "DATA_22_66") (pintype "bidirectional"))
    )
    (net (code "99") (name "Net-(U7B-DATA_23)") (class "Default")
      (node (ref "RN3") (pin "1") (pinfunction "1_1") (pintype "passive"))
      (node (ref "U7") (pin "67") (pinfunction "DATA_23_67") (pintype "bidirectional"))
    )
    (net (code "100") (name "Net-(U7B-DATA_24)") (class "Default")
      (node (ref "RN4") (pin "8") (pinfunction "8_8") (pintype "passive"))
      (node (ref "U7") (pin "69") (pinfunction "DATA_24_69") (pintype "bidirectional"))
    )
    (net (code "101") (name "Net-(U7B-DATA_25)") (class "Default")
      (node (ref "RN4") (pin "7") (pinfunction "7_7") (pintype "passive"))
      (node (ref "U7") (pin "70") (pinfunction "DATA_25_70") (pintype "bidirectional"))
    )
    (net (code "102") (name "Net-(U7B-DATA_26)") (class "Default")
      (node (ref "RN4") (pin "6") (pinfunction "6_6") (pintype "passive"))
      (node (ref "U7") (pin "71") (pinfunction "DATA_26_71") (pintype "bidirectional"))
    )
    (net (code "103") (name "Net-(U7B-DATA_27)") (class "Default")
      (node (ref "RN4") (pin "5") (pinfunction "5_5") (pintype "passive"))
      (node (ref "U7") (pin "72") (pinfunction "DATA_27_72") (pintype "bidirectional"))
    )
    (net (code "104") (name "Net-(U7B-DATA_28)") (class "Default")
      (node (ref "RN4") (pin "4") (pinfunction "4_4") (pintype "passive"))
      (node (ref "U7") (pin "73") (pinfunction "DATA_28_73") (pintype "bidirectional"))
    )
    (net (code "105") (name "Net-(U7B-DATA_29)") (class "Default")
      (node (ref "RN4") (pin "3") (pinfunction "3_3") (pintype "passive"))
      (node (ref "U7") (pin "74") (pinfunction "DATA_29_74") (pintype "bidirectional"))
    )
    (net (code "106") (name "Net-(U7B-DATA_30)") (class "Default")
      (node (ref "RN4") (pin "2") (pinfunction "2_2") (pintype "passive"))
      (node (ref "U7") (pin "75") (pinfunction "DATA_30_75") (pintype "bidirectional"))
    )
    (net (code "107") (name "Net-(U7B-DATA_31)") (class "Default")
      (node (ref "RN4") (pin "1") (pinfunction "1_1") (pintype "passive"))
      (node (ref "U7") (pin "76") (pinfunction "DATA_31_76") (pintype "bidirectional"))
    )
    (net (code "108") (name "Net-(U7B-RREF)") (class "Default")
      (node (ref "R100") (pin "2") (pinfunction "2_2") (pintype "passive"))
      (node (ref "U7") (pin "27") (pinfunction "RREF_27") (pintype "passive"))
    )
    (net (code "109") (name "Net-(U8-VIN)") (class "Default")
      (node (ref "FB2") (pin "2") (pinfunction "2_2") (pintype "passive"))
      (node (ref "U8") (pin "1") (pinfunction "VIN_1") (pintype "power_in"))
    )
    (net (code "110") (name "Net-(U8-VOUT)") (class "Default")
      (node (ref "C159") (pin "1") (pinfunction "1_1") (pintype "passive"))
      (node (ref "P2") (pin "1") (pinfunction "1_1") (pintype "passive"))
      (node (ref "TP11") (pin "1") (pinfunction "1_1") (pintype "passive"))
      (node (ref "U8") (pin "3") (pinfunction "VOUT_3") (pintype "power_in"))
    )
    (net (code "111") (name "USB3_VCC3P3") (class "Default")
      (node (ref "C147") (pin "1") (pinfunction "1_1") (pintype "passive"))
      (node (ref "C148") (pin "1") (pinfunction "1_1") (pintype "passive"))
      (node (ref "C149") (pin "1") (pinfunction "1_1") (pintype "passive"))
      (node (ref "C150") (pin "1") (pinfunction "1_1") (pintype "passive"))
      (node (ref "C151") (pin "1") (pinfunction "1_1") (pintype "passive"))
      (node (ref "C152") (pin "1") (pinfunction "1_1") (pintype "passive"))
      (node (ref "P2") (pin "2") (pinfunction "2_2") (pintype "passive"))
      (node (ref "U7") (pin "20") (pinfunction "VCC33_20") (pintype "power_in"))
      (node (ref "U7") (pin "24") (pinfunction "VCC33_24") (pintype "power_in"))
      (node (ref "U7") (pin "28") (pinfunction "VDDA_28") (pintype "power_in"))
      (node (ref "U7") (pin "38") (pinfunction "VCC33_38") (pintype "power_in"))
    )
    (net (code "112") (name "VBUS") (class "Default")
      (node (ref "C153") (pin "2") (pinfunction "2_2") (pintype "passive"))
      (node (ref "D13") (pin "1") (pinfunction "In_1_1") (pintype "passive"))
      (node (ref "FB2") (pin "1") (pinfunction "1_1") (pintype "passive"))
      (node (ref "J2") (pin "1") (pinfunction "VBUS_1") (pintype "passive"))
      (node (ref "R110") (pin "2") (pinfunction "2_2") (pintype "passive"))
    )
    (net (code "113") (name "VCC3P3") (class "Default")
      (node (ref "C137") (pin "1") (pinfunction "1_1") (pintype "passive"))
      (node (ref "C138") (pin "1") (pinfunction "1_1") (pintype "passive"))
      (node (ref "C139") (pin "1") (pinfunction "1_1") (pintype "passive"))
      (node (ref "C140") (pin "1") (pinfunction "1_1") (pintype "passive"))
      (node (ref "C143") (pin "1") (pinfunction "1_1") (pintype "passive"))
      (node (ref "C144") (pin "1") (pinfunction "1_1") (pintype "passive"))
      (node (ref "C145") (pin "1") (pinfunction "1_1") (pintype "passive"))
      (node (ref "C146") (pin "1") (pinfunction "1_1") (pintype "passive"))
      (node (ref "P2") (pin "3") (pinfunction "3_3") (pintype "passive"))
      (node (ref "R101") (pin "2") (pinfunction "2_2") (pintype "passive"))
      (node (ref "R102") (pin "2") (pinfunction "2_2") (pintype "passive"))
      (node (ref "R109") (pin "2") (pinfunction "2_2") (pintype "passive"))
      (node (ref "R112") (pin "2") (pinfunction "2_2") (pintype "passive"))
      (node (ref "R113") (pin "2") (pinfunction "2_2") (pintype "passive"))
      (node (ref "U7") (pin "14") (pinfunction "VCCIO_14") (pintype "power_in"))
      (node (ref "U7") (pin "49") (pinfunction "VCCIO_49") (pintype "power_in"))
      (node (ref "U7") (pin "59") (pinfunction "VCCIO_59") (pintype "power_in"))
      (node (ref "U7") (pin "68") (pinfunction "VCCIO_68") (pintype "power_in"))
    )
    (net (code "114") (name "VD10") (class "Default")
      (node (ref "C129") (pin "1") (pinfunction "1_1") (pintype "passive"))
      (node (ref "C130") (pin "1") (pinfunction "1_1") (pintype "passive"))
      (node (ref "C131") (pin "1") (pinfunction "1_1") (pintype "passive"))
      (node (ref "C132") (pin "2") (pinfunction "2_2") (pintype "passive"))
      (node (ref "C133") (pin "1") (pinfunction "1_1") (pintype "passive"))
      (node (ref "C134") (pin "1") (pinfunction "1_1") (pintype "passive"))
      (node (ref "C135") (pin "1") (pinfunction "1_1") (pintype "passive"))
      (node (ref "C136") (pin "1") (pinfunction "1_1") (pintype "passive"))
      (node (ref "FB1") (pin "2") (pinfunction "2_2") (pintype "passive"))
      (node (ref "TP9") (pin "1") (pinfunction "1_1") (pintype "passive"))
      (node (ref "U7") (pin "3") (pinfunction "VD10_3") (pintype "power_in"))
      (node (ref "U7") (pin "30") (pinfunction "VD10_30") (pintype "power_in"))
      (node (ref "U7") (pin "33") (pinfunction "VD10_33") (pintype "power_in"))
      (node (ref "U7") (pin "39") (pinfunction "DV10_39") (pintype "power_in"))
      (node (ref "U7") (pin "48") (pinfunction "VD10_48") (pintype "power_in"))
    )
    (net (code "115") (name "unconnected-(J2-ID-Pad4)") (class "Default")
      (node (ref "J2") (pin "4") (pinfunction "ID_4") (pintype "passive+no_connect"))
    )
  )
)
